# Block_Diagram.net
KiCad netlist of a schematic drawn in Altium Designer
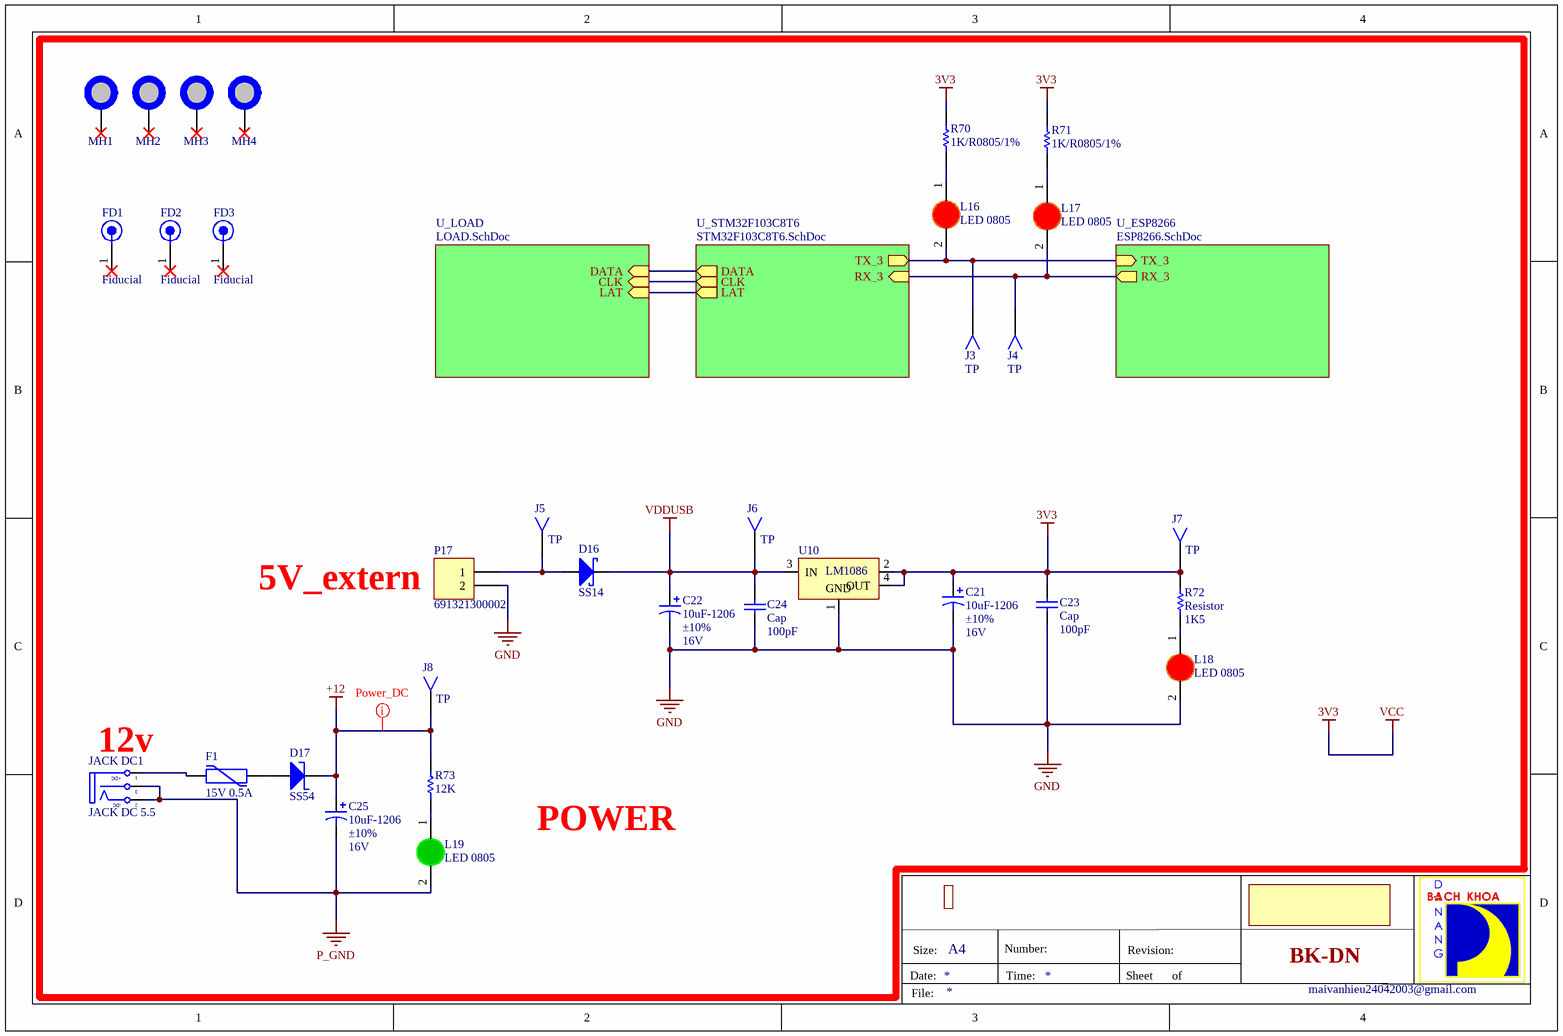
[diagram p0: Block_Diagram.SchDoc]

(export (version "E")
  (design (tool "Eeschema 10.0.6"))
  (components
    (comp (ref "C21")
      (value "10uF-1206")
      (footprint "CAP1206_TANTALUM_YELLOW")
      (description "CAP TANT 10UF 16V 10% 1206")
      (fields (field (name "TOLERANCE") "±10%") (field (name "VOLTAGE - RATED") "16V"))
      (libsource (lib "Indruino") (part "T491A106K016AT"))
    )
    (comp (ref "C22")
      (value "10uF-1206")
      (footprint "CAP1206_TANTALUM_YELLOW")
      (description "CAP TANT 10UF 16V 10% 1206")
      (fields (field (name "TOLERANCE") "±10%") (field (name "VOLTAGE - RATED") "16V"))
      (libsource (lib "Indruino") (part "T491A106K016AT"))
    )
    (comp (ref "C23")
      (value "Cap")
      (footprint "MinhTien_PcbLib:CAPC2012L")
      (description "Capacitor")
      (fields (field (name "ALTIUM_VALUE") "100pF") (field (name "PUBLISHER") "Altium Limited"))
      (libsource (lib "MinhTien_SCHLib") (part "Cap"))
    )
    (comp (ref "C24")
      (value "Cap")
      (footprint "MinhTien_PcbLib:CAPC2012L")
      (description "Capacitor")
      (fields (field (name "ALTIUM_VALUE") "100pF") (field (name "PUBLISHER") "Altium Limited"))
      (libsource (lib "MinhTien_SCHLib") (part "Cap"))
    )
    (comp (ref "C25")
      (value "10uF-1206")
      (footprint "CAP1206_TANTALUM_YELLOW")
      (description "CAP TANT 10UF 16V 10% 1206")
      (fields (field (name "TOLERANCE") "±10%") (field (name "VOLTAGE - RATED") "16V"))
      (libsource (lib "Indruino") (part "T491A106K016AT"))
    )
    (comp (ref "D16")
      (value "SS14")
      (footprint "DIODE SMD")
      (description "Dán")
      (libsource (lib "NhomLib") (part "Diode SS14 ( 1N5819)"))
    )
    (comp (ref "D17")
      (value "SS54")
      (footprint "DO-214AB/SMC")
      (libsource (lib "Mach Master") (part "Diode Schottky"))
    )
    (comp (ref "F1")
      (value "15V 0.5A")
      (footprint "Indruino:FUSE_PTC_SMD1812_02")
      (description "BOURNS         MF-MSMF110/16-2            FUSE, RESETTABLE PTC, 16V, 1.1A, 1812, FULL REEL")
      (fields (field (name "MANUFACTURER") "Bourns") (field (name "MANUFACTURER PART NUMBER") "MF-MSMF050-2"))
      (libsource (lib "Indruino") (part "FUSE_MF-MSMF050-2"))
    )
    (comp (ref "FD1")
      (value "Fiducial")
      (footprint "FIDUCIAL_TOP")
      (libsource (lib "MinhTien_SCHLib") (part "Fiducial"))
    )
    (comp (ref "FD2")
      (value "Fiducial")
      (footprint "FIDUCIAL_TOP")
      (libsource (lib "MinhTien_SCHLib") (part "Fiducial"))
    )
    (comp (ref "FD3")
      (value "Fiducial")
      (footprint "FIDUCIAL_TOP")
      (libsource (lib "MinhTien_SCHLib") (part "Fiducial"))
    )
    (comp (ref "J3")
      (value "TP")
      (footprint "Indruino:TEST_POINT_1.0X1.0MM")
      (fields (field (name "TOLERANCE") "±20%"))
      (libsource (lib "Indruino") (part "TEST POINT 1.0X1.0"))
    )
    (comp (ref "J4")
      (value "TP")
      (footprint "Indruino:TEST_POINT_1.0X1.0MM")
      (fields (field (name "TOLERANCE") "±20%"))
      (libsource (lib "Indruino") (part "TEST POINT 1.0X1.0"))
    )
    (comp (ref "J5")
      (value "TP")
      (footprint "Indruino:TEST_POINT_1.0X1.0MM")
      (fields (field (name "TOLERANCE") "±20%"))
      (libsource (lib "Indruino") (part "TEST POINT 1.0X1.0"))
    )
    (comp (ref "J6")
      (value "TP")
      (footprint "Indruino:TEST_POINT_1.0X1.0MM")
      (fields (field (name "TOLERANCE") "±20%"))
      (libsource (lib "Indruino") (part "TEST POINT 1.0X1.0"))
    )
    (comp (ref "J7")
      (value "TP")
      (footprint "Indruino:TEST_POINT_1.0X1.0MM")
      (fields (field (name "TOLERANCE") "±20%"))
      (libsource (lib "Indruino") (part "TEST POINT 1.0X1.0"))
    )
    (comp (ref "J8")
      (value "TP")
      (footprint "Indruino:TEST_POINT_1.0X1.0MM")
      (fields (field (name "TOLERANCE") "±20%"))
      (libsource (lib "Indruino") (part "TEST POINT 1.0X1.0"))
    )
    (comp (ref "JACK DC1")
      (value "JACK DC 5.5")
      (footprint "JACK DC 5.5")
      (libsource (lib "Medical_Box_1") (part "JACK DC 5.5"))
    )
    (comp (ref "L16")
      (value "LED 0805")
      (footprint "VHIEU_Passive:LED-RED-0805")
      (description "SMD")
      (libsource (lib "VHIEU_Passive") (part "LED RED 0805"))
    )
    (comp (ref "L17")
      (value "LED 0805")
      (footprint "VHIEU_Passive:LED-RED-0805")
      (description "SMD")
      (libsource (lib "VHIEU_Passive") (part "LED RED 0805"))
    )
    (comp (ref "L18")
      (value "LED 0805")
      (footprint "VHIEU_Passive:LED-RED-0805")
      (description "SMD")
      (libsource (lib "VHIEU_Passive") (part "LED RED 0805"))
    )
    (comp (ref "L19")
      (value "LED 0805")
      (footprint "VHIEU_Passive:LED-GREEN-0805")
      (description "SMD")
      (libsource (lib "VHIEU_Passive") (part "LED GREEN 0805"))
    )
    (comp (ref "MH1")
      (value "MH_3MMC_2.1MMD")
      (footprint "MH_3MMD_2.1MMD")
      (description "Mounting Hole 3mm Diameter, 2.1mm Drill")
      (libsource (lib "Indruino") (part "MH_3MMC_2.1MMD"))
    )
    (comp (ref "MH2")
      (value "MH_3MMC_2.1MMD")
      (footprint "MH_3MMD_2.1MMD")
      (description "Mounting Hole 3mm Diameter, 2.1mm Drill")
      (libsource (lib "Indruino") (part "MH_3MMC_2.1MMD"))
    )
    (comp (ref "MH3")
      (value "MH_3MMC_2.1MMD")
      (footprint "MH_3MMD_2.1MMD")
      (description "Mounting Hole 3mm Diameter, 2.1mm Drill")
      (libsource (lib "Indruino") (part "MH_3MMC_2.1MMD"))
    )
    (comp (ref "MH4")
      (value "MH_3MMC_2.1MMD")
      (footprint "MH_3MMD_2.1MMD")
      (description "Mounting Hole 3mm Diameter, 2.1mm Drill")
      (libsource (lib "Indruino") (part "MH_3MMC_2.1MMD"))
    )
    (comp (ref "P17")
      (value "691321300002")
      (footprint "TERMINAL_KF2EDGV_F_1X2_3.81")
      (description "TERM BLOCK HDR 2POS VERT 3.81MM")
      (fields (field (name "MANUFACTURER") "Wurth Electronics Inc."))
      (libsource (lib "KhanhBK_SCH_Lib_6") (part "TERMINAL_KF2EDGV_F_1X2_3.81"))
    )
    (comp (ref "R70")
      (value "1K/R0805/1%")
      (footprint "Res 0805 SMD")
      (description "1 kOhms ±1% 0.125W, 1/8W Chip Resistor 0805 (2012 Metric) Automotive AEC-Q200 Thick Film")
      (libsource (lib "Smart_home_1") (part "34.8K/R0805/1%_3"))
    )
    (comp (ref "R71")
      (value "1K/R0805/1%")
      (footprint "Res 0805 SMD")
      (description "1 kOhms ±1% 0.125W, 1/8W Chip Resistor 0805 (2012 Metric) Automotive AEC-Q200 Thick Film")
      (libsource (lib "Smart_home_1") (part "34.8K/R0805/1%_3"))
    )
    (comp (ref "R72")
      (value "Resistor")
      (footprint "MinhTien_PcbLib:RESC2012L")
      (description "Semiconductor Resistor")
      (fields (field (name "ALTIUM_VALUE") "1K5") (field (name "PUBLISHER") "Altium Limited"))
      (libsource (lib "MinhTien_SCHLib") (part "Resistor"))
    )
    (comp (ref "R73")
      (value "12K")
      (footprint "MinhTien_PcbLib:RESC2012L")
      (description "Semiconductor Resistor")
      (fields (field (name "Comment") "Resistor") (field (name "PUBLISHER") "Altium Limited"))
      (libsource (lib "MinhTien_SCHLib") (part "Resistor"))
    )
    (comp (ref "U10")
      (value "LM1086")
      (footprint "LPON_OTHER:LM1086")
      (description "Linear Voltage Regulator 3V3 1.5A 24V Max TO-220")
      (libsource (lib "lpson") (part "LM1086"))
    )
  )
  (nets
    (net (code "1") (name "+12") (class "Default")
      (node (ref "C25") (pin "1") (pinfunction "1_1") (pintype "passive"))
      (node (ref "D17") (pin "2") (pinfunction "K_2") (pintype "passive"))
      (node (ref "J8") (pin "1") (pinfunction "1_1") (pintype "passive"))
      (node (ref "R73") (pin "2") (pinfunction "2_2") (pintype "passive"))
    )
    (net (code "5") (name "/RX_3") (class "Default")
      (node (ref "J4") (pin "1") (pinfunction "1_1") (pintype "passive"))
      (node (ref "L17") (pin "2") (pinfunction "K_2") (pintype "passive"))
    )
    (net (code "6") (name "/TX_3") (class "Default")
      (node (ref "J3") (pin "1") (pinfunction "1_1") (pintype "passive"))
      (node (ref "L16") (pin "2") (pinfunction "K_2") (pintype "passive"))
    )
    (net (code "7") (name "3V3") (class "Default")
      (node (ref "C21") (pin "1") (pinfunction "1_1") (pintype "passive"))
      (node (ref "C23") (pin "1") (pinfunction "1_1") (pintype "passive"))
      (node (ref "J7") (pin "1") (pinfunction "1_1") (pintype "passive"))
      (node (ref "R70") (pin "2") (pinfunction "2_2") (pintype "passive"))
      (node (ref "R71") (pin "2") (pinfunction "2_2") (pintype "passive"))
      (node (ref "R72") (pin "1") (pinfunction "1_1") (pintype "passive"))
      (node (ref "U10") (pin "2") (pinfunction "OUT_2") (pintype "power_in"))
      (node (ref "U10") (pin "4") (pinfunction "OUT_4") (pintype "power_in"))
    )
    (net (code "8") (name "GND") (class "Default")
      (node (ref "C21") (pin "2") (pinfunction "2_2") (pintype "passive"))
      (node (ref "C22") (pin "2") (pinfunction "2_2") (pintype "passive"))
      (node (ref "C23") (pin "2") (pinfunction "2_2") (pintype "passive"))
      (node (ref "C24") (pin "2") (pinfunction "2_2") (pintype "passive"))
      (node (ref "L18") (pin "2") (pinfunction "K_2") (pintype "passive"))
      (node (ref "P17") (pin "2") (pinfunction "2_2") (pintype "passive"))
      (node (ref "U10") (pin "1") (pinfunction "GND_1") (pintype "power_in"))
    )
    (net (code "9") (name "Net-(D16-A)") (class "Default")
      (node (ref "D16") (pin "1") (pinfunction "A_1") (pintype "passive"))
      (node (ref "J5") (pin "1") (pinfunction "1_1") (pintype "passive"))
      (node (ref "P17") (pin "1") (pinfunction "1_1") (pintype "passive"))
    )
    (net (code "10") (name "Net-(D17-A)") (class "Default")
      (node (ref "D17") (pin "1") (pinfunction "A_1") (pintype "passive"))
      (node (ref "F1") (pin "2") (pinfunction "2_2") (pintype "passive"))
    )
    (net (code "11") (name "Net-(JACK DC1-T)") (class "Default")
      (node (ref "F1") (pin "1") (pinfunction "1_1") (pintype "passive"))
      (node (ref "JACK DC1") (pin "1") (pinfunction "T_1") (pintype "passive"))
    )
    (net (code "12") (name "Net-(L16-A)") (class "Default")
      (node (ref "L16") (pin "1") (pinfunction "A_1") (pintype "passive"))
      (node (ref "R70") (pin "1") (pinfunction "1_1") (pintype "passive"))
    )
    (net (code "13") (name "Net-(L17-A)") (class "Default")
      (node (ref "L17") (pin "1") (pinfunction "A_1") (pintype "passive"))
      (node (ref "R71") (pin "1") (pinfunction "1_1") (pintype "passive"))
    )
    (net (code "14") (name "Net-(L18-A)") (class "Default")
      (node (ref "L18") (pin "1") (pinfunction "A_1") (pintype "passive"))
      (node (ref "R72") (pin "2") (pinfunction "2_2") (pintype "passive"))
    )
    (net (code "15") (name "Net-(L19-A)") (class "Default")
      (node (ref "L19") (pin "1") (pinfunction "A_1") (pintype "passive"))
      (node (ref "R73") (pin "1") (pinfunction "1_1") (pintype "passive"))
    )
    (net (code "16") (name "P_GND") (class "Default")
      (node (ref "C25") (pin "2") (pinfunction "2_2") (pintype "passive"))
      (node (ref "JACK DC1") (pin "2") (pinfunction "TN_2") (pintype "passive"))
      (node (ref "JACK DC1") (pin "3") (pinfunction "S_3") (pintype "power_in"))
      (node (ref "L19") (pin "2") (pinfunction "K_2") (pintype "passive"))
    )
    (net (code "17") (name "VDDUSB") (class "Default")
      (node (ref "C22") (pin "1") (pinfunction "1_1") (pintype "passive"))
      (node (ref "C24") (pin "1") (pinfunction "1_1") (pintype "passive"))
      (node (ref "D16") (pin "2") (pinfunction "K_2") (pintype "passive"))
      (node (ref "J6") (pin "1") (pinfunction "1_1") (pintype "passive"))
      (node (ref "U10") (pin "3") (pinfunction "IN_3") (pintype "power_in"))
    )
    (net (code "18") (name "unconnected-(FD1-Pad1)") (class "Default")
      (node (ref "FD1") (pin "1") (pinfunction "1_1") (pintype "passive+no_connect"))
    )
    (net (code "19") (name "unconnected-(FD2-Pad1)") (class "Default")
      (node (ref "FD2") (pin "1") (pinfunction "1_1") (pintype "passive+no_connect"))
    )
    (net (code "20") (name "unconnected-(FD3-Pad1)") (class "Default")
      (node (ref "FD3") (pin "1") (pinfunction "1_1") (pintype "passive+no_connect"))
    )
    (net (code "21") (name "unconnected-(MH1-Pad1)") (class "Default")
      (node (ref "MH1") (pin "1") (pinfunction "1_1") (pintype "passive+no_connect"))
    )
    (net (code "22") (name "unconnected-(MH2-Pad1)") (class "Default")
      (node (ref "MH2") (pin "1") (pinfunction "1_1") (pintype "passive+no_connect"))
    )
    (net (code "23") (name "unconnected-(MH3-Pad1)") (class "Default")
      (node (ref "MH3") (pin "1") (pinfunction "1_1") (pintype "passive+no_connect"))
    )
    (net (code "24") (name "unconnected-(MH4-Pad1)") (class "Default")
      (node (ref "MH4") (pin "1") (pinfunction "1_1") (pintype "passive+no_connect"))
    )
  )
)
